# piezoampv10.net
KiCad netlist of a schematic drawn in EAGLE
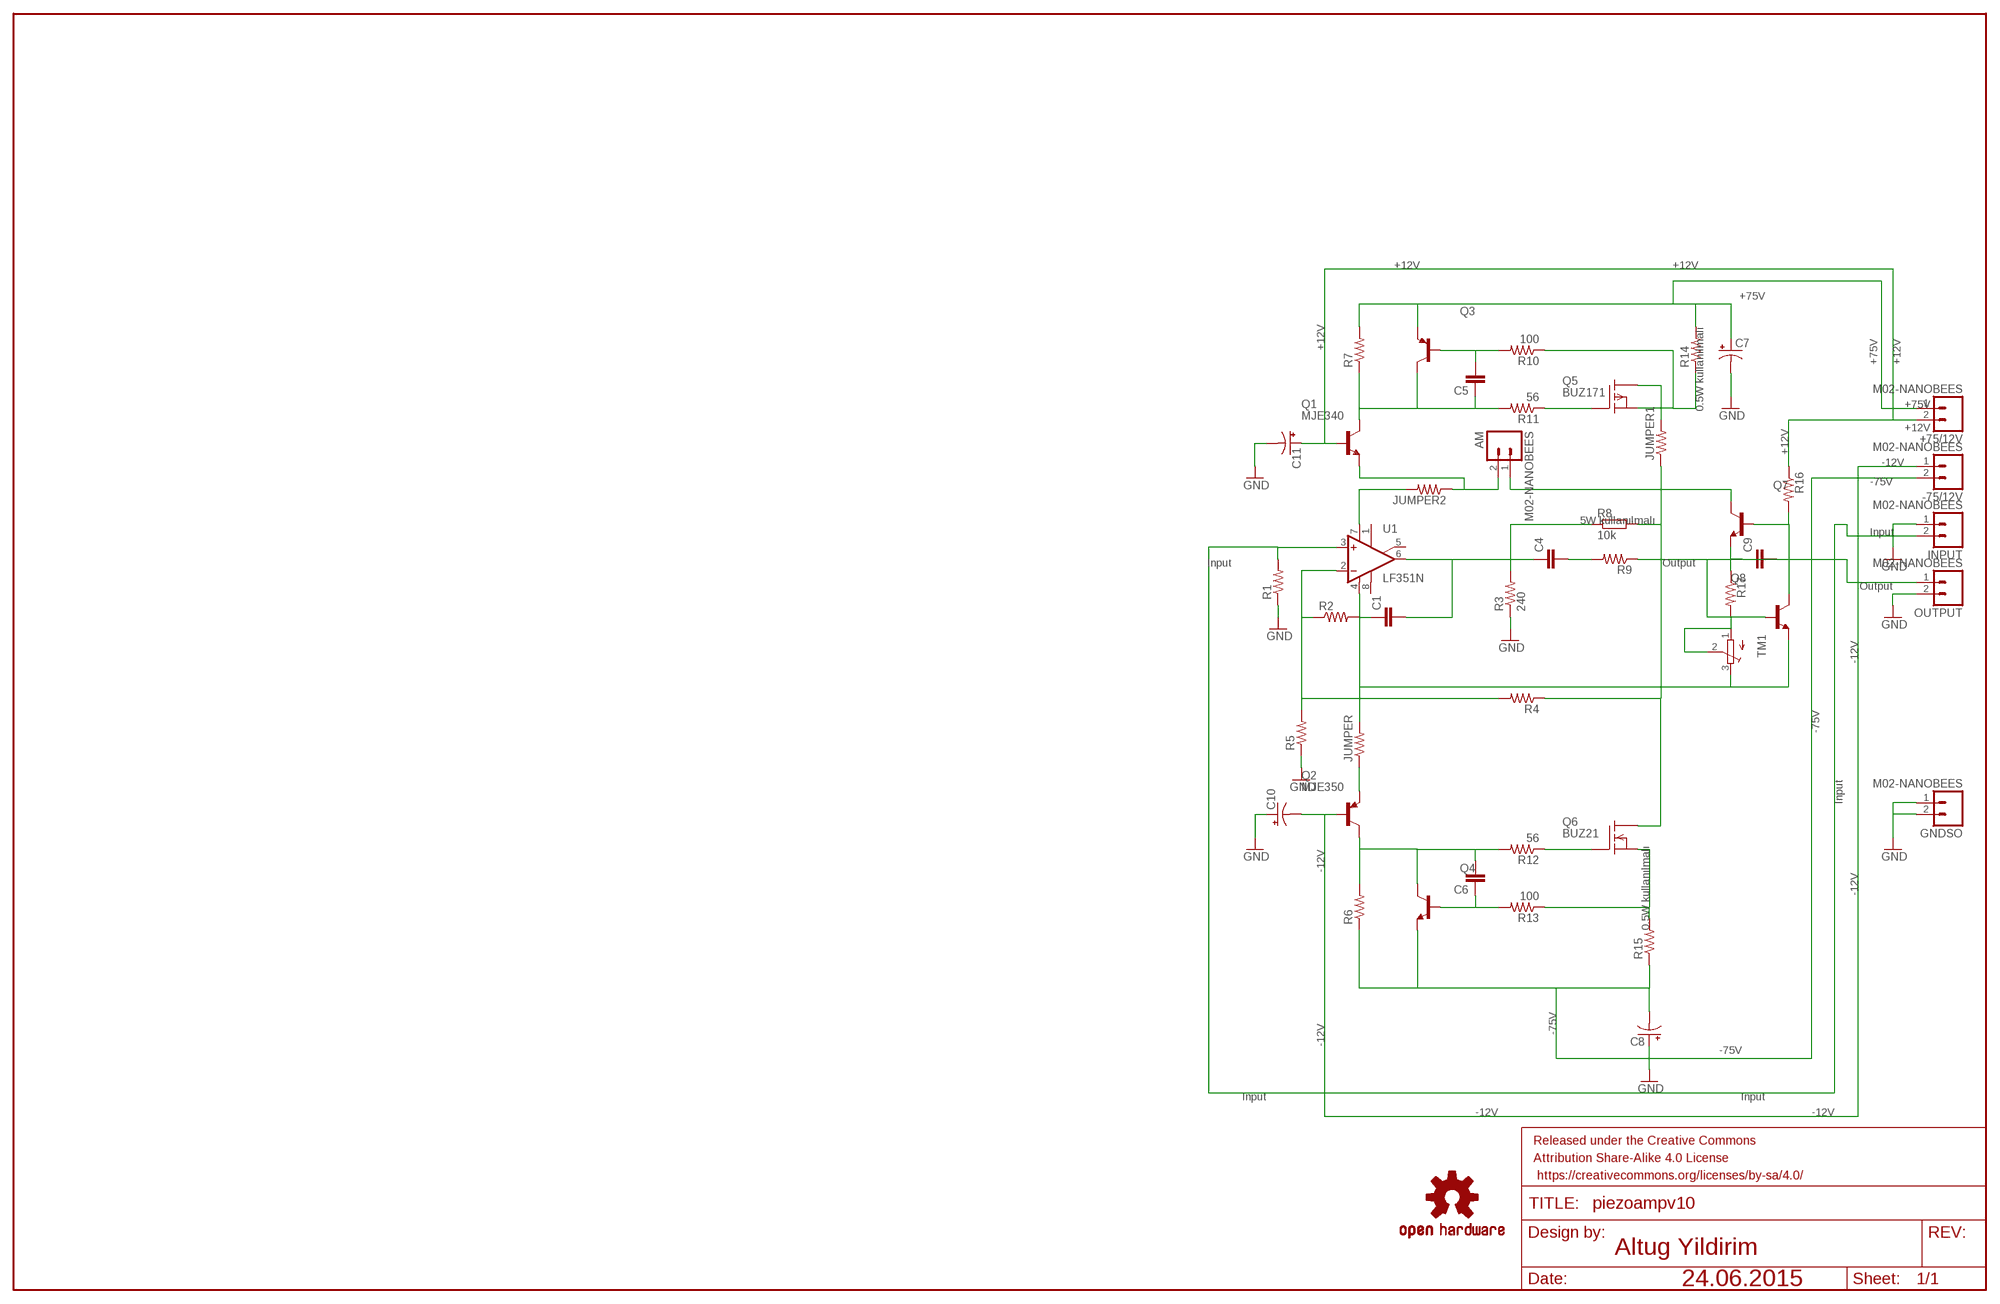
[diagram p0: schematic, sheet 1]

(export (version "E")
  (design (tool "Eeschema 10.0.6"))
  (components
    (comp (ref "+75/12V")
      (value "M02-NANOBEES")
      (footprint "eagle-import:M02-NANOBEES")
      (libsource (lib "eagle-import") (part "M02-NANOBEES"))
    )
    (comp (ref "-75/12V")
      (value "M02-NANOBEES")
      (footprint "eagle-import:M02-NANOBEES")
      (libsource (lib "eagle-import") (part "M02-NANOBEES"))
    )
    (comp (ref "AM")
      (value "M02-NANOBEES")
      (footprint "eagle-import:M02-NANOBEES")
      (libsource (lib "eagle-import") (part "M02-NANOBEES"))
    )
    (comp (ref "C1")
      (value "CAPPTH2")
      (footprint "eagle-import:CAP-PTH-SMALL2")
      (libsource (lib "eagle-import") (part "CAPPTH2"))
    )
    (comp (ref "C4")
      (value "CAPPTH2")
      (footprint "eagle-import:CAP-PTH-SMALL2")
      (libsource (lib "eagle-import") (part "CAPPTH2"))
    )
    (comp (ref "C5")
      (value "CAPPTH2")
      (footprint "eagle-import:CAP-PTH-SMALL2")
      (libsource (lib "eagle-import") (part "CAPPTH2"))
    )
    (comp (ref "C6")
      (value "CAPPTH2")
      (footprint "eagle-import:CAP-PTH-SMALL2")
      (libsource (lib "eagle-import") (part "CAPPTH2"))
    )
    (comp (ref "C7")
      (value "CAP_POLPTH3")
      (footprint "eagle-import:CPOL-RADIAL-1000UF-63V")
      (libsource (lib "eagle-import") (part "CAP_POLPTH3"))
    )
    (comp (ref "C8")
      (value "CAP_POLPTH3")
      (footprint "eagle-import:CPOL-RADIAL-1000UF-63V")
      (libsource (lib "eagle-import") (part "CAP_POLPTH3"))
    )
    (comp (ref "C9")
      (value "CAPPTH2")
      (footprint "eagle-import:CAP-PTH-SMALL2")
      (libsource (lib "eagle-import") (part "CAPPTH2"))
    )
    (comp (ref "C10")
      (value "CAP_POLPTH2")
      (footprint "eagle-import:CPOL-RADIAL-10UF-25V")
      (libsource (lib "eagle-import") (part "CAP_POLPTH2"))
    )
    (comp (ref "C11")
      (value "CAP_POLPTH2")
      (footprint "eagle-import:CPOL-RADIAL-10UF-25V")
      (libsource (lib "eagle-import") (part "CAP_POLPTH2"))
    )
    (comp (ref "FRAME1")
      (value "FRAME-LEDGER")
      (footprint "eagle-import:CREATIVE_COMMONS")
      (libsource (lib "eagle-import") (part "FRAME-LEDGER"))
    )
    (comp (ref "GNDSO")
      (value "M02-NANOBEES")
      (footprint "eagle-import:M02-NANOBEES")
      (libsource (lib "eagle-import") (part "M02-NANOBEES"))
    )
    (comp (ref "INPUT")
      (value "M02-NANOBEES")
      (footprint "eagle-import:M02-NANOBEES")
      (libsource (lib "eagle-import") (part "M02-NANOBEES"))
    )
    (comp (ref "JUMPER")
      (value "R-US_0204/7")
      (footprint "eagle-import:0204_7")
      (libsource (lib "eagle-import") (part "R-US_0204/7"))
    )
    (comp (ref "JUMPER1")
      (value "RESISTORPTH-1/4W")
      (footprint "eagle-import:AXIAL-0.4")
      (libsource (lib "eagle-import") (part "RESISTORPTH-1/4W"))
    )
    (comp (ref "JUMPER2")
      (value "R-US_0204/7")
      (footprint "eagle-import:0204_7")
      (libsource (lib "eagle-import") (part "R-US_0204/7"))
    )
    (comp (ref "LOGO1")
      (value "OSHW-LOGOM")
      (footprint "eagle-import:OSHW-LOGO-M")
      (libsource (lib "eagle-import") (part "OSHW-LOGOM"))
    )
    (comp (ref "OUTPUT")
      (value "M02-NANOBEES")
      (footprint "eagle-import:M02-NANOBEES")
      (libsource (lib "eagle-import") (part "M02-NANOBEES"))
    )
    (comp (ref "Q1")
      (value "MJE340")
      (footprint "eagle-import:TO126")
      (libsource (lib "eagle-import") (part "MJE340"))
    )
    (comp (ref "Q2")
      (value "MJE350")
      (footprint "eagle-import:TO126")
      (libsource (lib "eagle-import") (part "MJE350"))
    )
    (comp (ref "Q3")
      (value "BF421-PNP-TO92-BCE")
      (footprint "eagle-import:TO92-BCE")
      (libsource (lib "eagle-import") (part "-PNP-TO92-BCEBF421"))
    )
    (comp (ref "Q4")
      (value "-NPN-TO92-EBC")
      (footprint "eagle-import:TO92-EBC")
      (libsource (lib "eagle-import") (part "-NPN-TO92-EBC"))
    )
    (comp (ref "Q5")
      (value "BUZ171")
      (footprint "eagle-import:TO220")
      (libsource (lib "eagle-import") (part "BUZ171"))
    )
    (comp (ref "Q6")
      (value "BUZ21")
      (footprint "eagle-import:TO220")
      (libsource (lib "eagle-import") (part "BUZ21"))
    )
    (comp (ref "Q7")
      (value "-NPN-TO92-EBC")
      (footprint "eagle-import:TO92-EBC")
      (libsource (lib "eagle-import") (part "-NPN-TO92-EBC"))
    )
    (comp (ref "Q8")
      (value "-NPN-TO92-EBC")
      (footprint "eagle-import:TO92-EBC")
      (libsource (lib "eagle-import") (part "-NPN-TO92-EBC"))
    )
    (comp (ref "R1")
      (value "R-US_0204/7")
      (footprint "eagle-import:0204_7")
      (libsource (lib "eagle-import") (part "R-US_0204/7"))
    )
    (comp (ref "R2")
      (value "R-US_0204/7")
      (footprint "eagle-import:0204_7")
      (libsource (lib "eagle-import") (part "R-US_0204/7"))
    )
    (comp (ref "R3")
      (value "240")
      (footprint "eagle-import:0204_7")
      (libsource (lib "eagle-import") (part "R-US_0204/7"))
    )
    (comp (ref "R4")
      (value "R-US_0204/7")
      (footprint "eagle-import:0204_7")
      (libsource (lib "eagle-import") (part "R-US_0204/7"))
    )
    (comp (ref "R5")
      (value "R-US_0204/7")
      (footprint "eagle-import:0204_7")
      (libsource (lib "eagle-import") (part "R-US_0204/7"))
    )
    (comp (ref "R6")
      (value "R-US_0204/7")
      (footprint "eagle-import:0204_7")
      (libsource (lib "eagle-import") (part "R-US_0204/7"))
    )
    (comp (ref "R7")
      (value "R-US_0204/7")
      (footprint "eagle-import:0204_7")
      (libsource (lib "eagle-import") (part "R-US_0204/7"))
    )
    (comp (ref "R8")
      (value "10k")
      (footprint "eagle-import:P0817_22")
      (libsource (lib "eagle-import") (part "R-EU_0817/22"))
    )
    (comp (ref "R9")
      (value "R-US_0204/7")
      (footprint "eagle-import:0204_7")
      (libsource (lib "eagle-import") (part "R-US_0204/7"))
    )
    (comp (ref "R10")
      (value "100")
      (footprint "eagle-import:0204_7")
      (libsource (lib "eagle-import") (part "R-US_0204/7"))
    )
    (comp (ref "R11")
      (value "56")
      (footprint "eagle-import:0204_7")
      (libsource (lib "eagle-import") (part "R-US_0204/7"))
    )
    (comp (ref "R12")
      (value "56")
      (footprint "eagle-import:0204_7")
      (libsource (lib "eagle-import") (part "R-US_0204/7"))
    )
    (comp (ref "R13")
      (value "100")
      (footprint "eagle-import:0204_7")
      (libsource (lib "eagle-import") (part "R-US_0204/7"))
    )
    (comp (ref "R14")
      (value "RESISTORPTH-1/2W")
      (footprint "eagle-import:AXIAL-0.5")
      (libsource (lib "eagle-import") (part "RESISTORPTH-1/2W"))
    )
    (comp (ref "R15")
      (value "RESISTORPTH-1/2W")
      (footprint "eagle-import:AXIAL-0.5")
      (libsource (lib "eagle-import") (part "RESISTORPTH-1/2W"))
    )
    (comp (ref "R16")
      (value "R-US_0204/7")
      (footprint "eagle-import:0204_7")
      (libsource (lib "eagle-import") (part "R-US_0204/7"))
    )
    (comp (ref "R17")
      (value "R-US_0204/7")
      (footprint "eagle-import:0204_7")
      (libsource (lib "eagle-import") (part "R-US_0204/7"))
    )
    (comp (ref "TM1")
      (value "TRIMPOT3386")
      (footprint "eagle-import:TRIM-3386")
      (libsource (lib "eagle-import") (part "TRIMPOT3386"))
    )
    (comp (ref "U1")
      (value "LF351N")
      (footprint "eagle-import:DIL08")
      (libsource (lib "eagle-import") (part "LF351N"))
    )
  )
  (nets
    (net (code "1") (name "GND") (class "Default")
      (node (ref "C10") (pin "1") (pinfunction "+_1") (pintype "passive"))
      (node (ref "C11") (pin "2") (pinfunction "-_2") (pintype "passive"))
      (node (ref "C7") (pin "2") (pinfunction "-_2") (pintype "passive"))
      (node (ref "C8") (pin "1") (pinfunction "+_1") (pintype "passive"))
      (node (ref "GNDSO") (pin "1") (pinfunction "1_1") (pintype "passive"))
      (node (ref "GNDSO") (pin "2") (pinfunction "2_2") (pintype "passive"))
      (node (ref "INPUT") (pin "1") (pinfunction "1_1") (pintype "passive"))
      (node (ref "OUTPUT") (pin "2") (pinfunction "2_2") (pintype "passive"))
      (node (ref "R1") (pin "1") (pinfunction "1_1") (pintype "passive"))
      (node (ref "R3") (pin "1") (pinfunction "1_1") (pintype "passive"))
      (node (ref "R5") (pin "1") (pinfunction "1_1") (pintype "passive"))
    )
    (net (code "2") (name "Net-(AM-Pad1)") (class "Default")
      (node (ref "AM") (pin "1") (pinfunction "1_1") (pintype "passive"))
      (node (ref "Q7") (pin "C") (pinfunction "C_C") (pintype "passive"))
    )
    (net (code "3") (name "Net-(C1-Pad1)") (class "Default")
      (node (ref "C1") (pin "1") (pinfunction "1_1") (pintype "passive"))
      (node (ref "R2") (pin "2") (pinfunction "2_2") (pintype "passive"))
    )
    (net (code "4") (name "Net-(C4-Pad2)") (class "Default")
      (node (ref "C4") (pin "2") (pinfunction "2_2") (pintype "passive"))
      (node (ref "R9") (pin "2") (pinfunction "2_2") (pintype "passive"))
    )
    (net (code "5") (name "Net-(C5-Pad2)") (class "Default")
      (node (ref "C5") (pin "2") (pinfunction "2_2") (pintype "passive"))
      (node (ref "Q3") (pin "B") (pinfunction "B_B") (pintype "passive"))
      (node (ref "R10") (pin "2") (pinfunction "2_2") (pintype "passive"))
    )
    (net (code "6") (name "Net-(C6-Pad1)") (class "Default")
      (node (ref "C6") (pin "1") (pinfunction "1_1") (pintype "passive"))
      (node (ref "Q4") (pin "B") (pinfunction "B_B") (pintype "passive"))
      (node (ref "R13") (pin "2") (pinfunction "2_2") (pintype "passive"))
    )
    (net (code "7") (name "Net-(C7-+)") (class "Default")
      (node (ref "+75/12V") (pin "1") (pinfunction "1_1") (pintype "passive"))
      (node (ref "C7") (pin "1") (pinfunction "+_1") (pintype "passive"))
      (node (ref "Q3") (pin "E") (pinfunction "E_E") (pintype "passive"))
      (node (ref "R14") (pin "P$2") (pinfunction "2_P$2") (pintype "passive"))
      (node (ref "R7") (pin "2") (pinfunction "2_2") (pintype "passive"))
    )
    (net (code "8") (name "Net-(C8--)") (class "Default")
      (node (ref "-75/12V") (pin "2") (pinfunction "2_2") (pintype "passive"))
      (node (ref "C8") (pin "2") (pinfunction "-_2") (pintype "passive"))
      (node (ref "Q4") (pin "E") (pinfunction "E_E") (pintype "passive"))
      (node (ref "R15") (pin "P$1") (pinfunction "1_P$1") (pintype "passive"))
      (node (ref "R6") (pin "1") (pinfunction "1_1") (pintype "passive"))
    )
    (net (code "9") (name "Net-(C9-Pad1)") (class "Default")
      (node (ref "C9") (pin "1") (pinfunction "1_1") (pintype "passive"))
      (node (ref "Q7") (pin "E") (pinfunction "E_E") (pintype "passive"))
      (node (ref "Q8") (pin "B") (pinfunction "B_B") (pintype "passive"))
      (node (ref "R17") (pin "1") (pinfunction "1_1") (pintype "passive"))
    )
    (net (code "10") (name "Net-(C9-Pad2)") (class "Default")
      (node (ref "C9") (pin "2") (pinfunction "2_2") (pintype "passive"))
      (node (ref "Q7") (pin "B") (pinfunction "B_B") (pintype "passive"))
      (node (ref "Q8") (pin "C") (pinfunction "C_C") (pintype "passive"))
      (node (ref "R16") (pin "2") (pinfunction "2_2") (pintype "passive"))
    )
    (net (code "11") (name "Net-(C10--)") (class "Default")
      (node (ref "-75/12V") (pin "1") (pinfunction "1_1") (pintype "passive"))
      (node (ref "C10") (pin "2") (pinfunction "-_2") (pintype "passive"))
      (node (ref "Q2") (pin "3") (pinfunction "B_3") (pintype "passive"))
    )
    (net (code "12") (name "Net-(C11-+)") (class "Default")
      (node (ref "+75/12V") (pin "2") (pinfunction "2_2") (pintype "passive"))
      (node (ref "C11") (pin "1") (pinfunction "+_1") (pintype "passive"))
      (node (ref "Q1") (pin "3") (pinfunction "B_3") (pintype "passive"))
      (node (ref "R16") (pin "1") (pinfunction "1_1") (pintype "passive"))
    )
    (net (code "13") (name "Net-(JUMPER1-1)") (class "Default")
      (node (ref "JUMPER1") (pin "P$1") (pinfunction "1_P$1") (pintype "passive"))
      (node (ref "Q6") (pin "2") (pinfunction "D_2") (pintype "passive"))
      (node (ref "R4") (pin "1") (pinfunction "1_1") (pintype "passive"))
      (node (ref "R8") (pin "2") (pinfunction "2_2") (pintype "passive"))
    )
    (net (code "14") (name "Net-(JUMPER1-2)") (class "Default")
      (node (ref "JUMPER1") (pin "P$2") (pinfunction "2_P$2") (pintype "passive"))
      (node (ref "Q5") (pin "2") (pinfunction "D_2") (pintype "passive"))
    )
    (net (code "15") (name "Net-(OUTPUT-Pad1)") (class "Default")
      (node (ref "OUTPUT") (pin "1") (pinfunction "1_1") (pintype "passive"))
      (node (ref "R9") (pin "1") (pinfunction "1_1") (pintype "passive"))
    )
    (net (code "16") (name "Net-(Q1-C)") (class "Default")
      (node (ref "C5") (pin "1") (pinfunction "1_1") (pintype "passive"))
      (node (ref "Q1") (pin "2") (pinfunction "C_2") (pintype "passive"))
      (node (ref "Q3") (pin "C") (pinfunction "C_C") (pintype "passive"))
      (node (ref "R11") (pin "2") (pinfunction "2_2") (pintype "passive"))
      (node (ref "R7") (pin "1") (pinfunction "1_1") (pintype "passive"))
    )
    (net (code "17") (name "Net-(Q1-E)") (class "Default")
      (node (ref "AM") (pin "2") (pinfunction "2_2") (pintype "passive"))
      (node (ref "JUMPER2") (pin "1") (pinfunction "1_1") (pintype "passive"))
      (node (ref "Q1") (pin "1") (pinfunction "E_1") (pintype "passive"))
    )
    (net (code "18") (name "Net-(Q2-C)") (class "Default")
      (node (ref "C6") (pin "2") (pinfunction "2_2") (pintype "passive"))
      (node (ref "Q2") (pin "2") (pinfunction "C_2") (pintype "passive"))
      (node (ref "Q4") (pin "C") (pinfunction "C_C") (pintype "passive"))
      (node (ref "R12") (pin "2") (pinfunction "2_2") (pintype "passive"))
      (node (ref "R6") (pin "2") (pinfunction "2_2") (pintype "passive"))
    )
    (net (code "19") (name "Net-(Q2-E)") (class "Default")
      (node (ref "JUMPER") (pin "1") (pinfunction "1_1") (pintype "passive"))
      (node (ref "Q2") (pin "1") (pinfunction "E_1") (pintype "passive"))
    )
    (net (code "20") (name "Net-(Q5-G)") (class "Default")
      (node (ref "Q5") (pin "1") (pinfunction "G_1") (pintype "passive"))
      (node (ref "R11") (pin "1") (pinfunction "1_1") (pintype "passive"))
    )
    (net (code "21") (name "Net-(Q5-S)") (class "Default")
      (node (ref "Q5") (pin "3") (pinfunction "S_3") (pintype "passive"))
      (node (ref "R10") (pin "1") (pinfunction "1_1") (pintype "passive"))
      (node (ref "R14") (pin "P$1") (pinfunction "1_P$1") (pintype "passive"))
    )
    (net (code "22") (name "Net-(Q6-G)") (class "Default")
      (node (ref "Q6") (pin "1") (pinfunction "G_1") (pintype "passive"))
      (node (ref "R12") (pin "1") (pinfunction "1_1") (pintype "passive"))
    )
    (net (code "23") (name "Net-(Q6-S)") (class "Default")
      (node (ref "Q6") (pin "3") (pinfunction "S_3") (pintype "passive"))
      (node (ref "R13") (pin "1") (pinfunction "1_1") (pintype "passive"))
      (node (ref "R15") (pin "P$2") (pinfunction "2_P$2") (pintype "passive"))
    )
    (net (code "24") (name "Net-(TM1-A)") (class "Default")
      (node (ref "R17") (pin "2") (pinfunction "2_2") (pintype "passive"))
      (node (ref "TM1") (pin "1") (pinfunction "A_1") (pintype "passive"))
      (node (ref "TM1") (pin "2") (pinfunction "S_2") (pintype "passive"))
    )
    (net (code "25") (name "Net-(TM1-E)") (class "Default")
      (node (ref "JUMPER") (pin "2") (pinfunction "2_2") (pintype "passive"))
      (node (ref "Q8") (pin "E") (pinfunction "E_E") (pintype "passive"))
      (node (ref "TM1") (pin "3") (pinfunction "E_3") (pintype "passive"))
      (node (ref "U1") (pin "4") (pinfunction "V-_4") (pintype "power_in"))
    )
    (net (code "26") (name "Net-(U1-+IN)") (class "Default")
      (node (ref "INPUT") (pin "2") (pinfunction "2_2") (pintype "passive"))
      (node (ref "R1") (pin "2") (pinfunction "2_2") (pintype "passive"))
      (node (ref "U1") (pin "3") (pinfunction "+IN_3") (pintype "input"))
    )
    (net (code "27") (name "Net-(U1--IN)") (class "Default")
      (node (ref "R2") (pin "1") (pinfunction "1_1") (pintype "passive"))
      (node (ref "R4") (pin "2") (pinfunction "2_2") (pintype "passive"))
      (node (ref "R5") (pin "2") (pinfunction "2_2") (pintype "passive"))
      (node (ref "U1") (pin "2") (pinfunction "-IN_2") (pintype "input"))
    )
    (net (code "28") (name "Net-(U1-OUT)") (class "Default")
      (node (ref "C1") (pin "2") (pinfunction "2_2") (pintype "passive"))
      (node (ref "C4") (pin "1") (pinfunction "1_1") (pintype "passive"))
      (node (ref "R3") (pin "2") (pinfunction "2_2") (pintype "passive"))
      (node (ref "R8") (pin "1") (pinfunction "1_1") (pintype "passive"))
      (node (ref "U1") (pin "6") (pinfunction "OUT_6") (pintype "output"))
    )
    (net (code "29") (name "Net-(U1-V+)") (class "Default")
      (node (ref "JUMPER2") (pin "2") (pinfunction "2_2") (pintype "passive"))
      (node (ref "U1") (pin "7") (pinfunction "V+_7") (pintype "power_in"))
    )
    (net (code "30") (name "unconnected-(U1-ON1-Pad1)") (class "Default")
      (node (ref "U1") (pin "1") (pinfunction "ON1_1") (pintype "passive"))
    )
    (net (code "31") (name "unconnected-(U1-ON2-Pad5)") (class "Default")
      (node (ref "U1") (pin "5") (pinfunction "ON2_5") (pintype "passive"))
    )
    (net (code "32") (name "unconnected-(U1-OPT-Pad8)") (class "Default")
      (node (ref "U1") (pin "8") (pinfunction "OPT_8") (pintype "passive"))
    )
  )
)
